# ESP32_WROM_32.net
KiCad netlist of a schematic drawn in Altium Designer
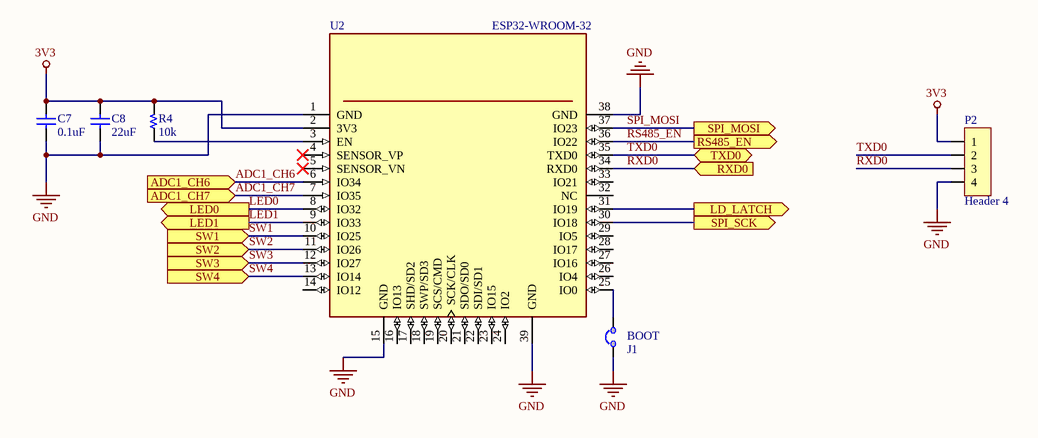
[diagram p0: ESP32_WROM_32.SchDoc]

(export (version "E")
  (design (tool "Eeschema 10.0.6"))
  (components
    (comp (ref "C7")
      (value "0.1uF")
      (footprint "C 0805")
      (description "Capacitor non-pol")
      (libsource (lib "chipfc_altium_libs") (part "Capacitor NP"))
    )
    (comp (ref "C8")
      (value "22uF")
      (footprint "C 0805")
      (description "Capacitor non-pol")
      (libsource (lib "chipfc_altium_libs") (part "Capacitor NP"))
    )
    (comp (ref "J1")
      (value "BOOT")
      (footprint "JUMP/2/Close")
      (libsource (lib "chipfc_altium_libs") (part "JUMP 2"))
    )
    (comp (ref "P2")
      (value "Header 4")
      (footprint "HDR/Header/4")
      (description "Header, 4-Pin")
      (libsource (lib "chipfc_altium_libs") (part "Header 4"))
    )
    (comp (ref "R4")
      (value "10k")
      (footprint "R 0805")
      (description "Resistor")
      (libsource (lib "chipfc_altium_libs") (part "Resistor"))
    )
    (comp (ref "U2")
      (value "ESP32-WROOM-32")
      (footprint "MODULE_ESP32-WROOM-32")
      (fields (field (name "MF") "Espressif Systems") (field (name "MP") "ESP32-WROOM-32D"))
      (libsource (lib "ESP32") (part "ESP32-WROOM-32"))
    )
  )
  (nets
    (net (code "1") (name "/ADC1_CH6") (class "Default")
      (node (ref "U2") (pin "6") (pinfunction "IO34_6") (pintype "input"))
    )
    (net (code "2") (name "/ADC1_CH7") (class "Default")
      (node (ref "U2") (pin "7") (pinfunction "IO35_7") (pintype "input"))
    )
    (net (code "3") (name "/LD_LATCH") (class "Default")
      (node (ref "U2") (pin "31") (pinfunction "IO19_31") (pintype "bidirectional"))
    )
    (net (code "4") (name "/LED0") (class "Default")
      (node (ref "U2") (pin "8") (pinfunction "IO32_8") (pintype "bidirectional"))
    )
    (net (code "5") (name "/LED1") (class "Default")
      (node (ref "U2") (pin "9") (pinfunction "IO33_9") (pintype "bidirectional"))
    )
    (net (code "6") (name "/RS485_EN") (class "Default")
      (node (ref "U2") (pin "36") (pinfunction "IO22_36") (pintype "bidirectional"))
    )
    (net (code "7") (name "/RXD0") (class "Default")
      (node (ref "P2") (pin "3") (pinfunction "3_3") (pintype "passive"))
      (node (ref "U2") (pin "34") (pinfunction "RXD0_34") (pintype "bidirectional"))
    )
    (net (code "8") (name "/SPI_MOSI") (class "Default")
      (node (ref "U2") (pin "37") (pinfunction "IO23_37") (pintype "bidirectional"))
    )
    (net (code "9") (name "/SPI_SCK") (class "Default")
      (node (ref "U2") (pin "30") (pinfunction "IO18_30") (pintype "bidirectional"))
    )
    (net (code "10") (name "/SW1") (class "Default")
      (node (ref "U2") (pin "10") (pinfunction "IO25_10") (pintype "bidirectional"))
    )
    (net (code "11") (name "/SW2") (class "Default")
      (node (ref "U2") (pin "11") (pinfunction "IO26_11") (pintype "bidirectional"))
    )
    (net (code "12") (name "/SW3") (class "Default")
      (node (ref "U2") (pin "12") (pinfunction "IO27_12") (pintype "bidirectional"))
    )
    (net (code "13") (name "/SW4") (class "Default")
      (node (ref "U2") (pin "13") (pinfunction "IO14_13") (pintype "bidirectional"))
    )
    (net (code "14") (name "/TXD0") (class "Default")
      (node (ref "P2") (pin "2") (pinfunction "2_2") (pintype "passive"))
      (node (ref "U2") (pin "35") (pinfunction "TXD0_35") (pintype "bidirectional"))
    )
    (net (code "15") (name "3V3") (class "Default")
      (node (ref "C7") (pin "1") (pinfunction "1_1") (pintype "passive"))
      (node (ref "C8") (pin "1") (pinfunction "1_1") (pintype "passive"))
      (node (ref "P2") (pin "1") (pinfunction "1_1") (pintype "passive"))
      (node (ref "R4") (pin "2") (pinfunction "2_2") (pintype "passive"))
      (node (ref "U2") (pin "2") (pinfunction "3V3_2") (pintype "power_in"))
    )
    (net (code "16") (name "GND") (class "Default")
      (node (ref "C7") (pin "2") (pinfunction "2_2") (pintype "passive"))
      (node (ref "C8") (pin "2") (pinfunction "2_2") (pintype "passive"))
      (node (ref "J1") (pin "1") (pinfunction "1_1") (pintype "passive"))
      (node (ref "P2") (pin "4") (pinfunction "4_4") (pintype "passive"))
      (node (ref "U2") (pin "1") (pinfunction "GND_1") (pintype "power_in"))
      (node (ref "U2") (pin "15") (pinfunction "GND_15") (pintype "power_in"))
      (node (ref "U2") (pin "38") (pinfunction "GND_38") (pintype "power_in"))
      (node (ref "U2") (pin "39") (pinfunction "GND_39") (pintype "power_in"))
    )
    (net (code "17") (name "Net-(U2-EN)") (class "Default")
      (node (ref "R4") (pin "1") (pinfunction "1_1") (pintype "passive"))
      (node (ref "U2") (pin "3") (pinfunction "EN_3") (pintype "input"))
    )
    (net (code "18") (name "Net-(U2-IO0)") (class "Default")
      (node (ref "J1") (pin "2") (pinfunction "2_2") (pintype "passive"))
      (node (ref "U2") (pin "25") (pinfunction "IO0_25") (pintype "bidirectional"))
    )
    (net (code "19") (name "unconnected-(U2-IO2-Pad24)") (class "Default")
      (node (ref "U2") (pin "24") (pinfunction "IO2_24") (pintype "bidirectional"))
    )
    (net (code "20") (name "unconnected-(U2-IO4-Pad26)") (class "Default")
      (node (ref "U2") (pin "26") (pinfunction "IO4_26") (pintype "bidirectional"))
    )
    (net (code "21") (name "unconnected-(U2-IO5-Pad29)") (class "Default")
      (node (ref "U2") (pin "29") (pinfunction "IO5_29") (pintype "bidirectional"))
    )
    (net (code "22") (name "unconnected-(U2-IO12-Pad14)") (class "Default")
      (node (ref "U2") (pin "14") (pinfunction "IO12_14") (pintype "bidirectional"))
    )
    (net (code "23") (name "unconnected-(U2-IO13-Pad16)") (class "Default")
      (node (ref "U2") (pin "16") (pinfunction "IO13_16") (pintype "bidirectional"))
    )
    (net (code "24") (name "unconnected-(U2-IO15-Pad23)") (class "Default")
      (node (ref "U2") (pin "23") (pinfunction "IO15_23") (pintype "bidirectional"))
    )
    (net (code "25") (name "unconnected-(U2-IO16-Pad27)") (class "Default")
      (node (ref "U2") (pin "27") (pinfunction "IO16_27") (pintype "bidirectional"))
    )
    (net (code "26") (name "unconnected-(U2-IO17-Pad28)") (class "Default")
      (node (ref "U2") (pin "28") (pinfunction "IO17_28") (pintype "bidirectional"))
    )
    (net (code "27") (name "unconnected-(U2-IO21-Pad33)") (class "Default")
      (node (ref "U2") (pin "33") (pinfunction "IO21_33") (pintype "bidirectional"))
    )
    (net (code "28") (name "unconnected-(U2-NC-Pad32)") (class "Default")
      (node (ref "U2") (pin "32") (pinfunction "NC_32") (pintype "power_in"))
    )
    (net (code "29") (name "unconnected-(U2-SCK{slash}CLK-Pad20)") (class "Default")
      (node (ref "U2") (pin "20") (pinfunction "SCK/CLK_20") (pintype "bidirectional"))
    )
    (net (code "30") (name "unconnected-(U2-SCS{slash}CMD-Pad19)") (class "Default")
      (node (ref "U2") (pin "19") (pinfunction "SCS/CMD_19") (pintype "bidirectional"))
    )
    (net (code "31") (name "unconnected-(U2-SDI{slash}SD1-Pad22)") (class "Default")
      (node (ref "U2") (pin "22") (pinfunction "SDI/SD1_22") (pintype "bidirectional"))
    )
    (net (code "32") (name "unconnected-(U2-SDO{slash}SD0-Pad21)") (class "Default")
      (node (ref "U2") (pin "21") (pinfunction "SDO/SD0_21") (pintype "bidirectional"))
    )
    (net (code "33") (name "unconnected-(U2-SENSOR_VN-Pad5)") (class "Default")
      (node (ref "U2") (pin "5") (pinfunction "SENSOR_VN_5") (pintype "input+no_connect"))
    )
    (net (code "34") (name "unconnected-(U2-SENSOR_VP-Pad4)") (class "Default")
      (node (ref "U2") (pin "4") (pinfunction "SENSOR_VP_4") (pintype "input+no_connect"))
    )
    (net (code "35") (name "unconnected-(U2-SHD{slash}SD2-Pad17)") (class "Default")
      (node (ref "U2") (pin "17") (pinfunction "SHD/SD2_17") (pintype "bidirectional"))
    )
    (net (code "36") (name "unconnected-(U2-SWP{slash}SD3-Pad18)") (class "Default")
      (node (ref "U2") (pin "18") (pinfunction "SWP/SD3_18") (pintype "bidirectional"))
    )
  )
)
